# Iridium_9603N_Test_Header.net
KiCad netlist of a schematic drawn in EAGLE
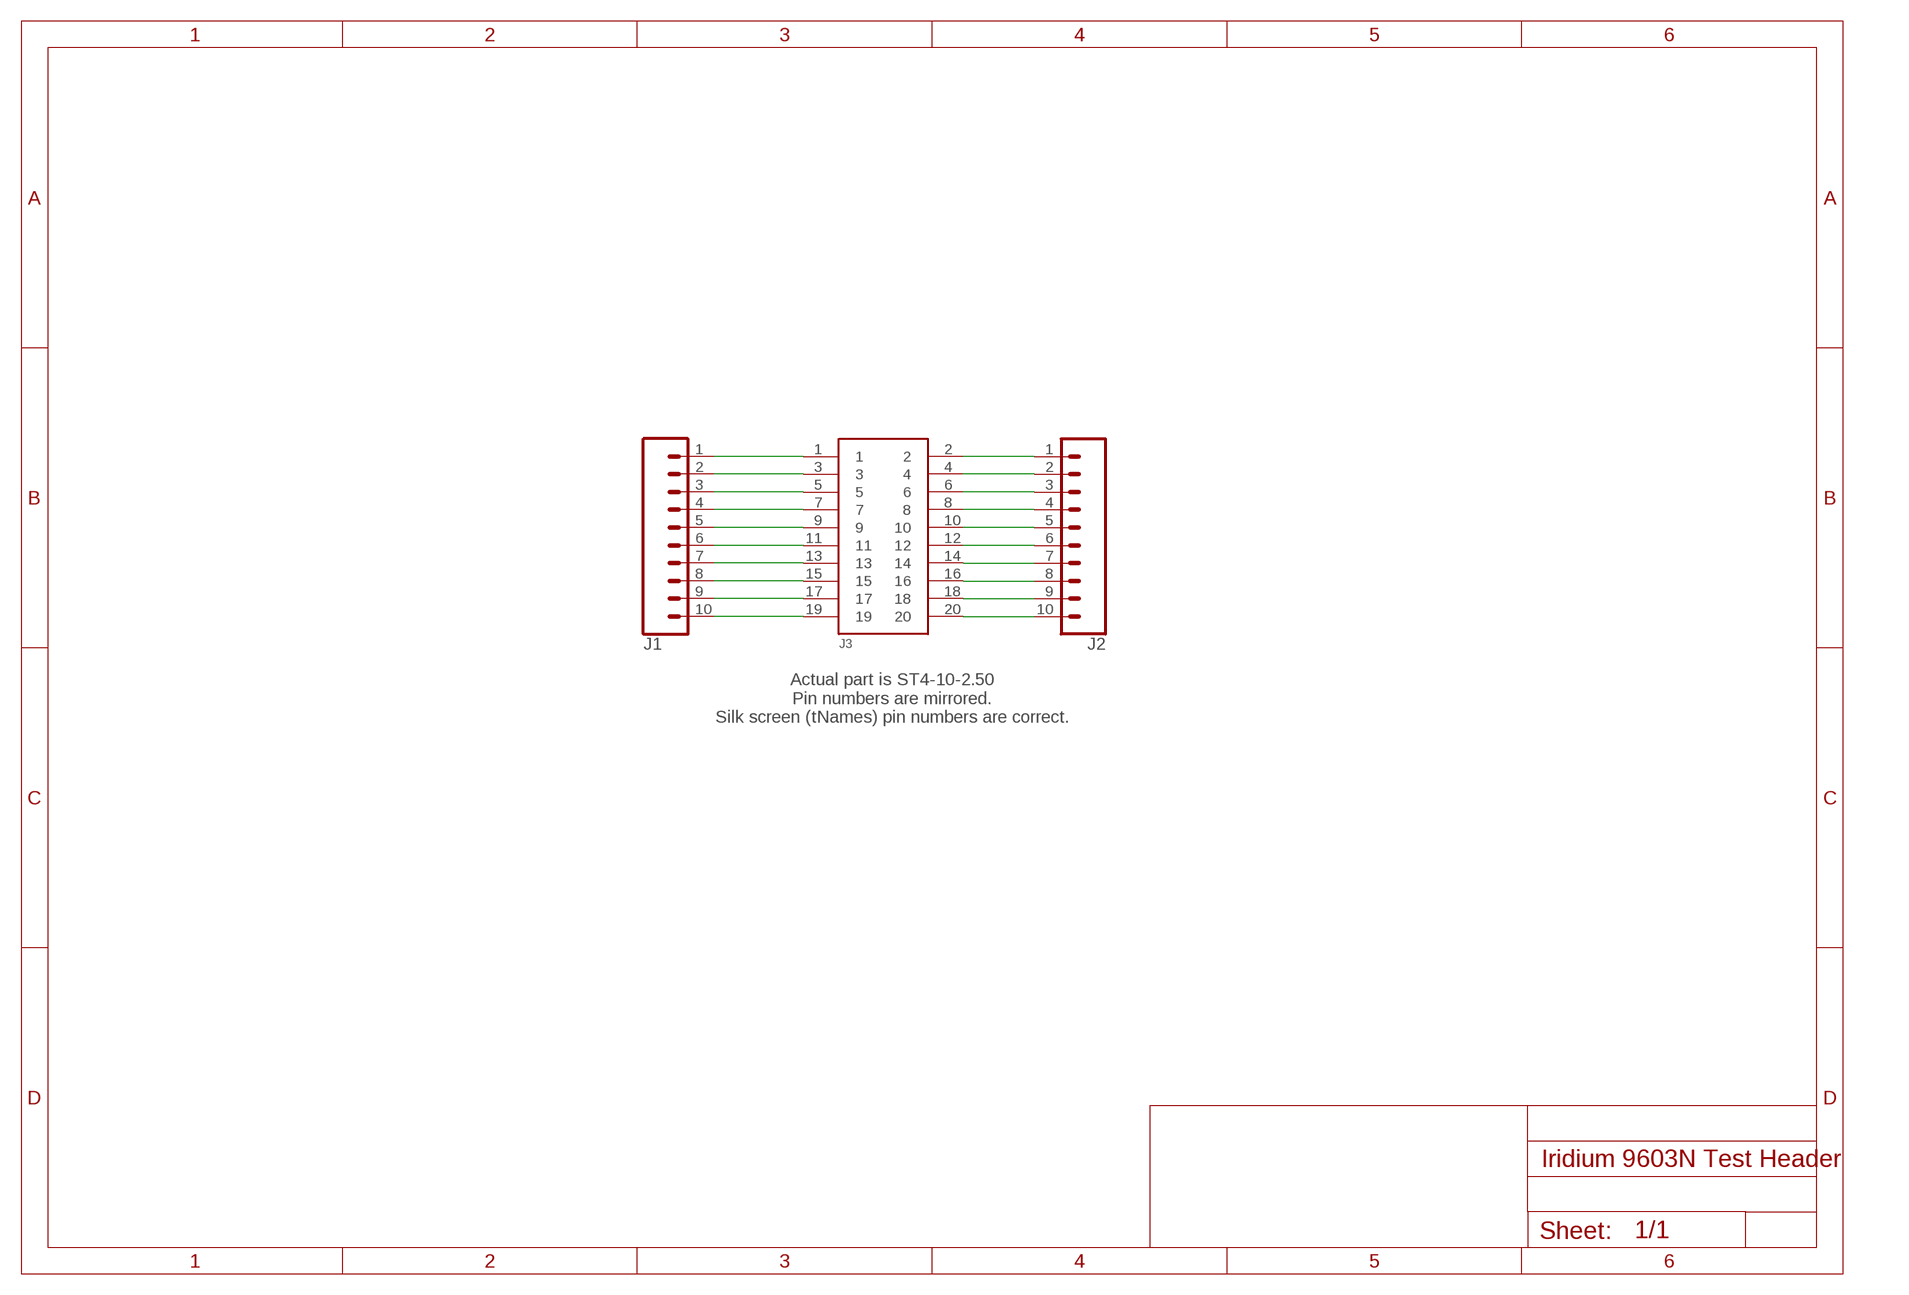
[diagram p0: schematic, sheet 1]

(export (version "E")
  (design (tool "Eeschema 10.0.6"))
  (components
    (comp (ref "J1")
      (value "CONN_10\"")
      (footprint "eagle-import:1X10")
      (libsource (lib "eagle-import") (part "CONN_10{dblquote}"))
    )
    (comp (ref "J2")
      (value "CONN_10\"")
      (footprint "eagle-import:1X10")
      (libsource (lib "eagle-import") (part "CONN_10{dblquote}"))
    )
    (comp (ref "J3")
      (value "SS4-10-3.50-X-D")
      (footprint "eagle-import:SS4-10-3.50-X-D")
      (libsource (lib "eagle-import") (part "SS4-10-3.50-X-D"))
    )
  )
  (nets
    (net (code "1") (name "Net-(J1-Pad1)") (class "Default")
      (node (ref "J1") (pin "1") (pinfunction "1_1") (pintype "passive"))
      (node (ref "J3") (pin "1") (pinfunction "1_1") (pintype "bidirectional"))
    )
    (net (code "2") (name "Net-(J1-Pad2)") (class "Default")
      (node (ref "J1") (pin "2") (pinfunction "2_2") (pintype "passive"))
      (node (ref "J3") (pin "3") (pinfunction "3_3") (pintype "bidirectional"))
    )
    (net (code "3") (name "Net-(J1-Pad3)") (class "Default")
      (node (ref "J1") (pin "3") (pinfunction "3_3") (pintype "passive"))
      (node (ref "J3") (pin "5") (pinfunction "5_5") (pintype "bidirectional"))
    )
    (net (code "4") (name "Net-(J1-Pad4)") (class "Default")
      (node (ref "J1") (pin "4") (pinfunction "4_4") (pintype "passive"))
      (node (ref "J3") (pin "7") (pinfunction "7_7") (pintype "bidirectional"))
    )
    (net (code "5") (name "Net-(J1-Pad5)") (class "Default")
      (node (ref "J1") (pin "5") (pinfunction "5_5") (pintype "passive"))
      (node (ref "J3") (pin "9") (pinfunction "9_9") (pintype "bidirectional"))
    )
    (net (code "6") (name "Net-(J1-Pad6)") (class "Default")
      (node (ref "J1") (pin "6") (pinfunction "6_6") (pintype "passive"))
      (node (ref "J3") (pin "11") (pinfunction "11_11") (pintype "bidirectional"))
    )
    (net (code "7") (name "Net-(J1-Pad7)") (class "Default")
      (node (ref "J1") (pin "7") (pinfunction "7_7") (pintype "passive"))
      (node (ref "J3") (pin "13") (pinfunction "13_13") (pintype "bidirectional"))
    )
    (net (code "8") (name "Net-(J1-Pad8)") (class "Default")
      (node (ref "J1") (pin "8") (pinfunction "8_8") (pintype "passive"))
      (node (ref "J3") (pin "15") (pinfunction "15_15") (pintype "bidirectional"))
    )
    (net (code "9") (name "Net-(J1-Pad9)") (class "Default")
      (node (ref "J1") (pin "9") (pinfunction "9_9") (pintype "passive"))
      (node (ref "J3") (pin "17") (pinfunction "17_17") (pintype "bidirectional"))
    )
    (net (code "10") (name "Net-(J1-Pad10)") (class "Default")
      (node (ref "J1") (pin "10") (pinfunction "10_10") (pintype "passive"))
      (node (ref "J3") (pin "19") (pinfunction "19_19") (pintype "bidirectional"))
    )
    (net (code "11") (name "Net-(J2-Pad1)") (class "Default")
      (node (ref "J2") (pin "1") (pinfunction "1_1") (pintype "passive"))
      (node (ref "J3") (pin "2") (pinfunction "2_2") (pintype "bidirectional"))
    )
    (net (code "12") (name "Net-(J2-Pad2)") (class "Default")
      (node (ref "J2") (pin "2") (pinfunction "2_2") (pintype "passive"))
      (node (ref "J3") (pin "4") (pinfunction "4_4") (pintype "bidirectional"))
    )
    (net (code "13") (name "Net-(J2-Pad3)") (class "Default")
      (node (ref "J2") (pin "3") (pinfunction "3_3") (pintype "passive"))
      (node (ref "J3") (pin "6") (pinfunction "6_6") (pintype "bidirectional"))
    )
    (net (code "14") (name "Net-(J2-Pad4)") (class "Default")
      (node (ref "J2") (pin "4") (pinfunction "4_4") (pintype "passive"))
      (node (ref "J3") (pin "8") (pinfunction "8_8") (pintype "bidirectional"))
    )
    (net (code "15") (name "Net-(J2-Pad5)") (class "Default")
      (node (ref "J2") (pin "5") (pinfunction "5_5") (pintype "passive"))
      (node (ref "J3") (pin "10") (pinfunction "10_10") (pintype "bidirectional"))
    )
    (net (code "16") (name "Net-(J2-Pad6)") (class "Default")
      (node (ref "J2") (pin "6") (pinfunction "6_6") (pintype "passive"))
      (node (ref "J3") (pin "12") (pinfunction "12_12") (pintype "bidirectional"))
    )
    (net (code "17") (name "Net-(J2-Pad7)") (class "Default")
      (node (ref "J2") (pin "7") (pinfunction "7_7") (pintype "passive"))
      (node (ref "J3") (pin "14") (pinfunction "14_14") (pintype "bidirectional"))
    )
    (net (code "18") (name "Net-(J2-Pad8)") (class "Default")
      (node (ref "J2") (pin "8") (pinfunction "8_8") (pintype "passive"))
      (node (ref "J3") (pin "16") (pinfunction "16_16") (pintype "bidirectional"))
    )
    (net (code "19") (name "Net-(J2-Pad9)") (class "Default")
      (node (ref "J2") (pin "9") (pinfunction "9_9") (pintype "passive"))
      (node (ref "J3") (pin "18") (pinfunction "18_18") (pintype "bidirectional"))
    )
    (net (code "20") (name "Net-(J2-Pad10)") (class "Default")
      (node (ref "J2") (pin "10") (pinfunction "10_10") (pintype "passive"))
      (node (ref "J3") (pin "20") (pinfunction "20_20") (pintype "bidirectional"))
    )
  )
)
